# drivers.net
KiCad netlist of a schematic drawn in Altium Designer
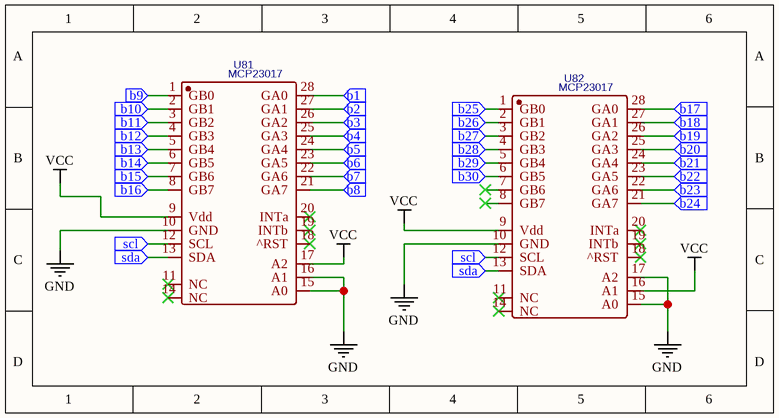
[diagram p0: drivers.schdoc]

(export (version "E")
  (design (tool "Eeschema 10.0.6"))
  (components
    (comp (ref "U81")
      (value "MCP23017")
      (fields (field (name "CONTRIBUTOR") "tsvstar"))
      (libsource (lib "altium-import") (part "root_0_MCP23017_"))
    )
    (comp (ref "U82")
      (value "MCP23017")
      (fields (field (name "CONTRIBUTOR") "tsvstar"))
      (libsource (lib "altium-import") (part "root_0_MCP23017_"))
    )
  )
  (nets
    (net (code "1") (name "/b1") (class "Default")
      (node (ref "U81") (pin "28") (pinfunction "GA0_28") (pintype "passive"))
    )
    (net (code "2") (name "/b2") (class "Default")
      (node (ref "U81") (pin "27") (pinfunction "GA1_27") (pintype "passive"))
    )
    (net (code "3") (name "/b3") (class "Default")
      (node (ref "U81") (pin "26") (pinfunction "GA2_26") (pintype "passive"))
    )
    (net (code "4") (name "/b4") (class "Default")
      (node (ref "U81") (pin "25") (pinfunction "GA3_25") (pintype "passive"))
    )
    (net (code "5") (name "/b5") (class "Default")
      (node (ref "U81") (pin "24") (pinfunction "GA4_24") (pintype "passive"))
    )
    (net (code "6") (name "/b6") (class "Default")
      (node (ref "U81") (pin "23") (pinfunction "GA5_23") (pintype "passive"))
    )
    (net (code "7") (name "/b7") (class "Default")
      (node (ref "U81") (pin "22") (pinfunction "GA6_22") (pintype "passive"))
    )
    (net (code "8") (name "/b8") (class "Default")
      (node (ref "U81") (pin "21") (pinfunction "GA7_21") (pintype "passive"))
    )
    (net (code "9") (name "/b9") (class "Default")
      (node (ref "U81") (pin "1") (pinfunction "GB0_1") (pintype "passive"))
    )
    (net (code "10") (name "/b10") (class "Default")
      (node (ref "U81") (pin "2") (pinfunction "GB1_2") (pintype "passive"))
    )
    (net (code "11") (name "/b11") (class "Default")
      (node (ref "U81") (pin "3") (pinfunction "GB2_3") (pintype "passive"))
    )
    (net (code "12") (name "/b12") (class "Default")
      (node (ref "U81") (pin "4") (pinfunction "GB3_4") (pintype "passive"))
    )
    (net (code "13") (name "/b13") (class "Default")
      (node (ref "U81") (pin "5") (pinfunction "GB4_5") (pintype "passive"))
    )
    (net (code "14") (name "/b14") (class "Default")
      (node (ref "U81") (pin "6") (pinfunction "GB5_6") (pintype "passive"))
    )
    (net (code "15") (name "/b15") (class "Default")
      (node (ref "U81") (pin "7") (pinfunction "GB6_7") (pintype "passive"))
    )
    (net (code "16") (name "/b16") (class "Default")
      (node (ref "U81") (pin "8") (pinfunction "GB7_8") (pintype "passive"))
    )
    (net (code "17") (name "/b17") (class "Default")
      (node (ref "U82") (pin "28") (pinfunction "GA0_28") (pintype "passive"))
    )
    (net (code "18") (name "/b18") (class "Default")
      (node (ref "U82") (pin "27") (pinfunction "GA1_27") (pintype "passive"))
    )
    (net (code "19") (name "/b19") (class "Default")
      (node (ref "U82") (pin "26") (pinfunction "GA2_26") (pintype "passive"))
    )
    (net (code "20") (name "/b20") (class "Default")
      (node (ref "U82") (pin "25") (pinfunction "GA3_25") (pintype "passive"))
    )
    (net (code "21") (name "/b21") (class "Default")
      (node (ref "U82") (pin "24") (pinfunction "GA4_24") (pintype "passive"))
    )
    (net (code "22") (name "/b22") (class "Default")
      (node (ref "U82") (pin "23") (pinfunction "GA5_23") (pintype "passive"))
    )
    (net (code "23") (name "/b23") (class "Default")
      (node (ref "U82") (pin "22") (pinfunction "GA6_22") (pintype "passive"))
    )
    (net (code "24") (name "/b24") (class "Default")
      (node (ref "U82") (pin "21") (pinfunction "GA7_21") (pintype "passive"))
    )
    (net (code "25") (name "/b25") (class "Default")
      (node (ref "U82") (pin "1") (pinfunction "GB0_1") (pintype "passive"))
    )
    (net (code "26") (name "/b26") (class "Default")
      (node (ref "U82") (pin "2") (pinfunction "GB1_2") (pintype "passive"))
    )
    (net (code "27") (name "/b27") (class "Default")
      (node (ref "U82") (pin "3") (pinfunction "GB2_3") (pintype "passive"))
    )
    (net (code "28") (name "/b28") (class "Default")
      (node (ref "U82") (pin "4") (pinfunction "GB3_4") (pintype "passive"))
    )
    (net (code "29") (name "/b29") (class "Default")
      (node (ref "U82") (pin "5") (pinfunction "GB4_5") (pintype "passive"))
    )
    (net (code "30") (name "/b30") (class "Default")
      (node (ref "U82") (pin "6") (pinfunction "GB5_6") (pintype "passive"))
    )
    (net (code "31") (name "/scl") (class "Default")
      (node (ref "U81") (pin "12") (pinfunction "SCL_12") (pintype "passive"))
      (node (ref "U82") (pin "12") (pinfunction "SCL_12") (pintype "passive"))
    )
    (net (code "32") (name "/sda") (class "Default")
      (node (ref "U81") (pin "13") (pinfunction "SDA_13") (pintype "passive"))
      (node (ref "U82") (pin "13") (pinfunction "SDA_13") (pintype "passive"))
    )
    (net (code "33") (name "GND") (class "Default")
      (node (ref "U81") (pin "10") (pinfunction "GND_10") (pintype "passive"))
      (node (ref "U81") (pin "15") (pinfunction "A0_15") (pintype "passive"))
      (node (ref "U81") (pin "16") (pinfunction "A1_16") (pintype "passive"))
      (node (ref "U82") (pin "10") (pinfunction "GND_10") (pintype "passive"))
      (node (ref "U82") (pin "15") (pinfunction "A0_15") (pintype "passive"))
      (node (ref "U82") (pin "17") (pinfunction "A2_17") (pintype "passive"))
    )
    (net (code "34") (name "VCC") (class "Default")
      (node (ref "U81") (pin "17") (pinfunction "A2_17") (pintype "passive"))
      (node (ref "U81") (pin "9") (pinfunction "Vdd_9") (pintype "passive"))
      (node (ref "U82") (pin "16") (pinfunction "A1_16") (pintype "passive"))
      (node (ref "U82") (pin "9") (pinfunction "Vdd_9") (pintype "passive"))
    )
    (net (code "35") (name "unconnected-(U81-INTa-Pad20)") (class "Default")
      (node (ref "U81") (pin "20") (pinfunction "INTa_20") (pintype "passive+no_connect"))
    )
    (net (code "36") (name "unconnected-(U81-INTb-Pad19)") (class "Default")
      (node (ref "U81") (pin "19") (pinfunction "INTb_19") (pintype "passive+no_connect"))
    )
    (net (code "37") (name "unconnected-(U81-NC-Pad11)") (class "Default")
      (node (ref "U81") (pin "11") (pinfunction "NC_11") (pintype "passive+no_connect"))
    )
    (net (code "38") (name "unconnected-(U81-NC-Pad14)") (class "Default")
      (node (ref "U81") (pin "14") (pinfunction "NC_14") (pintype "passive+no_connect"))
    )
    (net (code "39") (name "unconnected-(U81-^RST-Pad18)") (class "Default")
      (node (ref "U81") (pin "18") (pinfunction "^RST_18") (pintype "passive+no_connect"))
    )
    (net (code "40") (name "unconnected-(U82-GB6-Pad7)") (class "Default")
      (node (ref "U82") (pin "7") (pinfunction "GB6_7") (pintype "passive+no_connect"))
    )
    (net (code "41") (name "unconnected-(U82-GB7-Pad8)") (class "Default")
      (node (ref "U82") (pin "8") (pinfunction "GB7_8") (pintype "passive+no_connect"))
    )
    (net (code "42") (name "unconnected-(U82-INTa-Pad20)") (class "Default")
      (node (ref "U82") (pin "20") (pinfunction "INTa_20") (pintype "passive+no_connect"))
    )
    (net (code "43") (name "unconnected-(U82-INTb-Pad19)") (class "Default")
      (node (ref "U82") (pin "19") (pinfunction "INTb_19") (pintype "passive+no_connect"))
    )
    (net (code "44") (name "unconnected-(U82-NC-Pad11)") (class "Default")
      (node (ref "U82") (pin "11") (pinfunction "NC_11") (pintype "passive+no_connect"))
    )
    (net (code "45") (name "unconnected-(U82-NC-Pad14)") (class "Default")
      (node (ref "U82") (pin "14") (pinfunction "NC_14") (pintype "passive+no_connect"))
    )
    (net (code "46") (name "unconnected-(U82-^RST-Pad18)") (class "Default")
      (node (ref "U82") (pin "18") (pinfunction "^RST_18") (pintype "passive+no_connect"))
    )
  )
)
